# Trafo_schematic.net
KiCad netlist of a schematic drawn in EAGLE
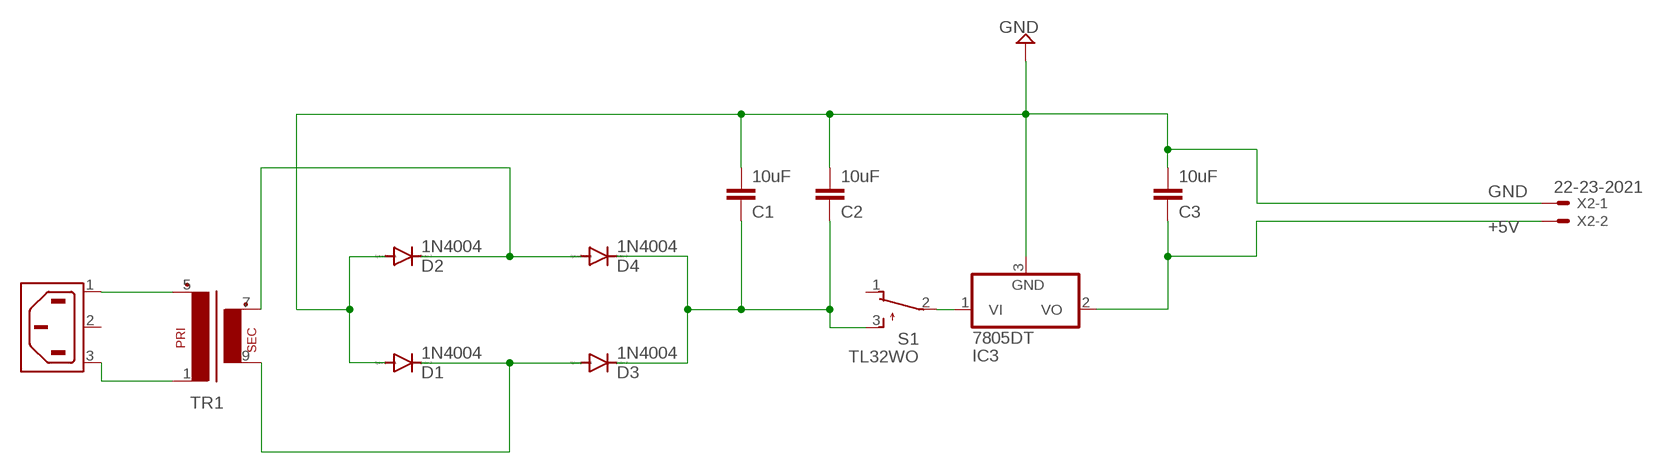
[diagram p0: schematic, sheet 1]

(export (version "E")
  (design (tool "Eeschema 10.0.6"))
  (components
    (comp (ref "C1")
      (value "10uF")
      (footprint "eagle-import:C2.5-2")
      (libsource (lib "eagle-import") (part "C2.5/2"))
    )
    (comp (ref "C2")
      (value "10uF")
      (footprint "eagle-import:C2.5-2")
      (libsource (lib "eagle-import") (part "C2.5/2"))
    )
    (comp (ref "C3")
      (value "10uF")
      (footprint "eagle-import:C2.5-2")
      (libsource (lib "eagle-import") (part "C2.5/2"))
    )
    (comp (ref "D1")
      (value "1N4004")
      (footprint "eagle-import:DO41-10")
      (libsource (lib "eagle-import") (part "1N4004"))
    )
    (comp (ref "D2")
      (value "1N4004")
      (footprint "eagle-import:DO41-10")
      (libsource (lib "eagle-import") (part "1N4004"))
    )
    (comp (ref "D3")
      (value "1N4004")
      (footprint "eagle-import:DO41-10")
      (libsource (lib "eagle-import") (part "1N4004"))
    )
    (comp (ref "D4")
      (value "1N4004")
      (footprint "eagle-import:DO41-10")
      (libsource (lib "eagle-import") (part "1N4004"))
    )
    (comp (ref "IC3")
      (value "7805DT")
      (footprint "eagle-import:TO252")
      (libsource (lib "eagle-import") (part "78DT05"))
    )
    (comp (ref "S1")
      (value "TL32WO")
      (footprint "eagle-import:TL3XWO")
      (libsource (lib "eagle-import") (part "TL32WO"))
    )
    (comp (ref "TR1")
      (value "EI30-1")
      (footprint "eagle-import:EI30-1")
      (libsource (lib "eagle-import") (part "EI30-1"))
    )
    (comp (ref "X1")
      (value "6ESRM-P")
      (footprint "eagle-import:6ESRM-P")
      (fields (field (name "MF") "TYCO ELECTRONICS"))
      (libsource (lib "eagle-import") (part "6ESRM-P"))
    )
    (comp (ref "X2")
      (value "22-23-2021")
      (footprint "eagle-import:22-23-2021")
      (fields (field (name "MF") "MOLEX"))
      (libsource (lib "eagle-import") (part "22-23-2021"))
    )
  )
  (nets
    (net (code "1") (name "/+5V") (class "Default")
      (node (ref "C3") (pin "1") (pinfunction "1_1") (pintype "passive"))
      (node (ref "IC3") (pin "2") (pinfunction "VO_2") (pintype "passive"))
      (node (ref "X2") (pin "2") (pinfunction "S_2") (pintype "passive"))
    )
    (net (code "2") (name "GND") (class "Default")
      (node (ref "C1") (pin "2") (pinfunction "2_2") (pintype "passive"))
      (node (ref "C2") (pin "2") (pinfunction "2_2") (pintype "passive"))
      (node (ref "C3") (pin "2") (pinfunction "2_2") (pintype "passive"))
      (node (ref "D1") (pin "A") (pinfunction "A_A") (pintype "passive"))
      (node (ref "D2") (pin "A") (pinfunction "A_A") (pintype "passive"))
      (node (ref "IC3") (pin "3") (pinfunction "GND_3") (pintype "passive"))
      (node (ref "X2") (pin "1") (pinfunction "S_1") (pintype "passive"))
    )
    (net (code "3") (name "Net-(IC3-VI)") (class "Default")
      (node (ref "IC3") (pin "1") (pinfunction "VI_1") (pintype "input"))
      (node (ref "S1") (pin "2") (pinfunction "P_2") (pintype "passive"))
    )
    (net (code "4") (name "Net-(S1-S)") (class "Default")
      (node (ref "C1") (pin "1") (pinfunction "1_1") (pintype "passive"))
      (node (ref "C2") (pin "1") (pinfunction "1_1") (pintype "passive"))
      (node (ref "D3") (pin "C") (pinfunction "C_C") (pintype "passive"))
      (node (ref "D4") (pin "C") (pinfunction "C_C") (pintype "passive"))
      (node (ref "S1") (pin "3") (pinfunction "S_3") (pintype "passive"))
    )
    (net (code "5") (name "Net-(TR1-P1)") (class "Default")
      (node (ref "TR1") (pin "1") (pinfunction "P1_1") (pintype "passive"))
      (node (ref "X1") (pin "3") (pinfunction "AC2_3") (pintype "passive"))
    )
    (net (code "6") (name "Net-(TR1-P2)") (class "Default")
      (node (ref "TR1") (pin "5") (pinfunction "P2_5") (pintype "passive"))
      (node (ref "X1") (pin "1") (pinfunction "AC1_1") (pintype "passive"))
    )
    (net (code "7") (name "Net-(TR1-S3)") (class "Default")
      (node (ref "D2") (pin "C") (pinfunction "C_C") (pintype "passive"))
      (node (ref "D4") (pin "A") (pinfunction "A_A") (pintype "passive"))
      (node (ref "TR1") (pin "7") (pinfunction "S3_7") (pintype "passive"))
    )
    (net (code "8") (name "Net-(TR1-S4)") (class "Default")
      (node (ref "D1") (pin "C") (pinfunction "C_C") (pintype "passive"))
      (node (ref "D3") (pin "A") (pinfunction "A_A") (pintype "passive"))
      (node (ref "TR1") (pin "9") (pinfunction "S4_9") (pintype "passive"))
    )
    (net (code "9") (name "unconnected-(S1-O-Pad1)") (class "Default")
      (node (ref "S1") (pin "1") (pinfunction "O_1") (pintype "passive"))
    )
    (net (code "10") (name "unconnected-(X1-SH-Pad2)") (class "Default")
      (node (ref "X1") (pin "2") (pinfunction "SH_2") (pintype "passive"))
    )
  )
)
